# STM32_CAN-USB.net
KiCad netlist of a schematic drawn in EAGLE
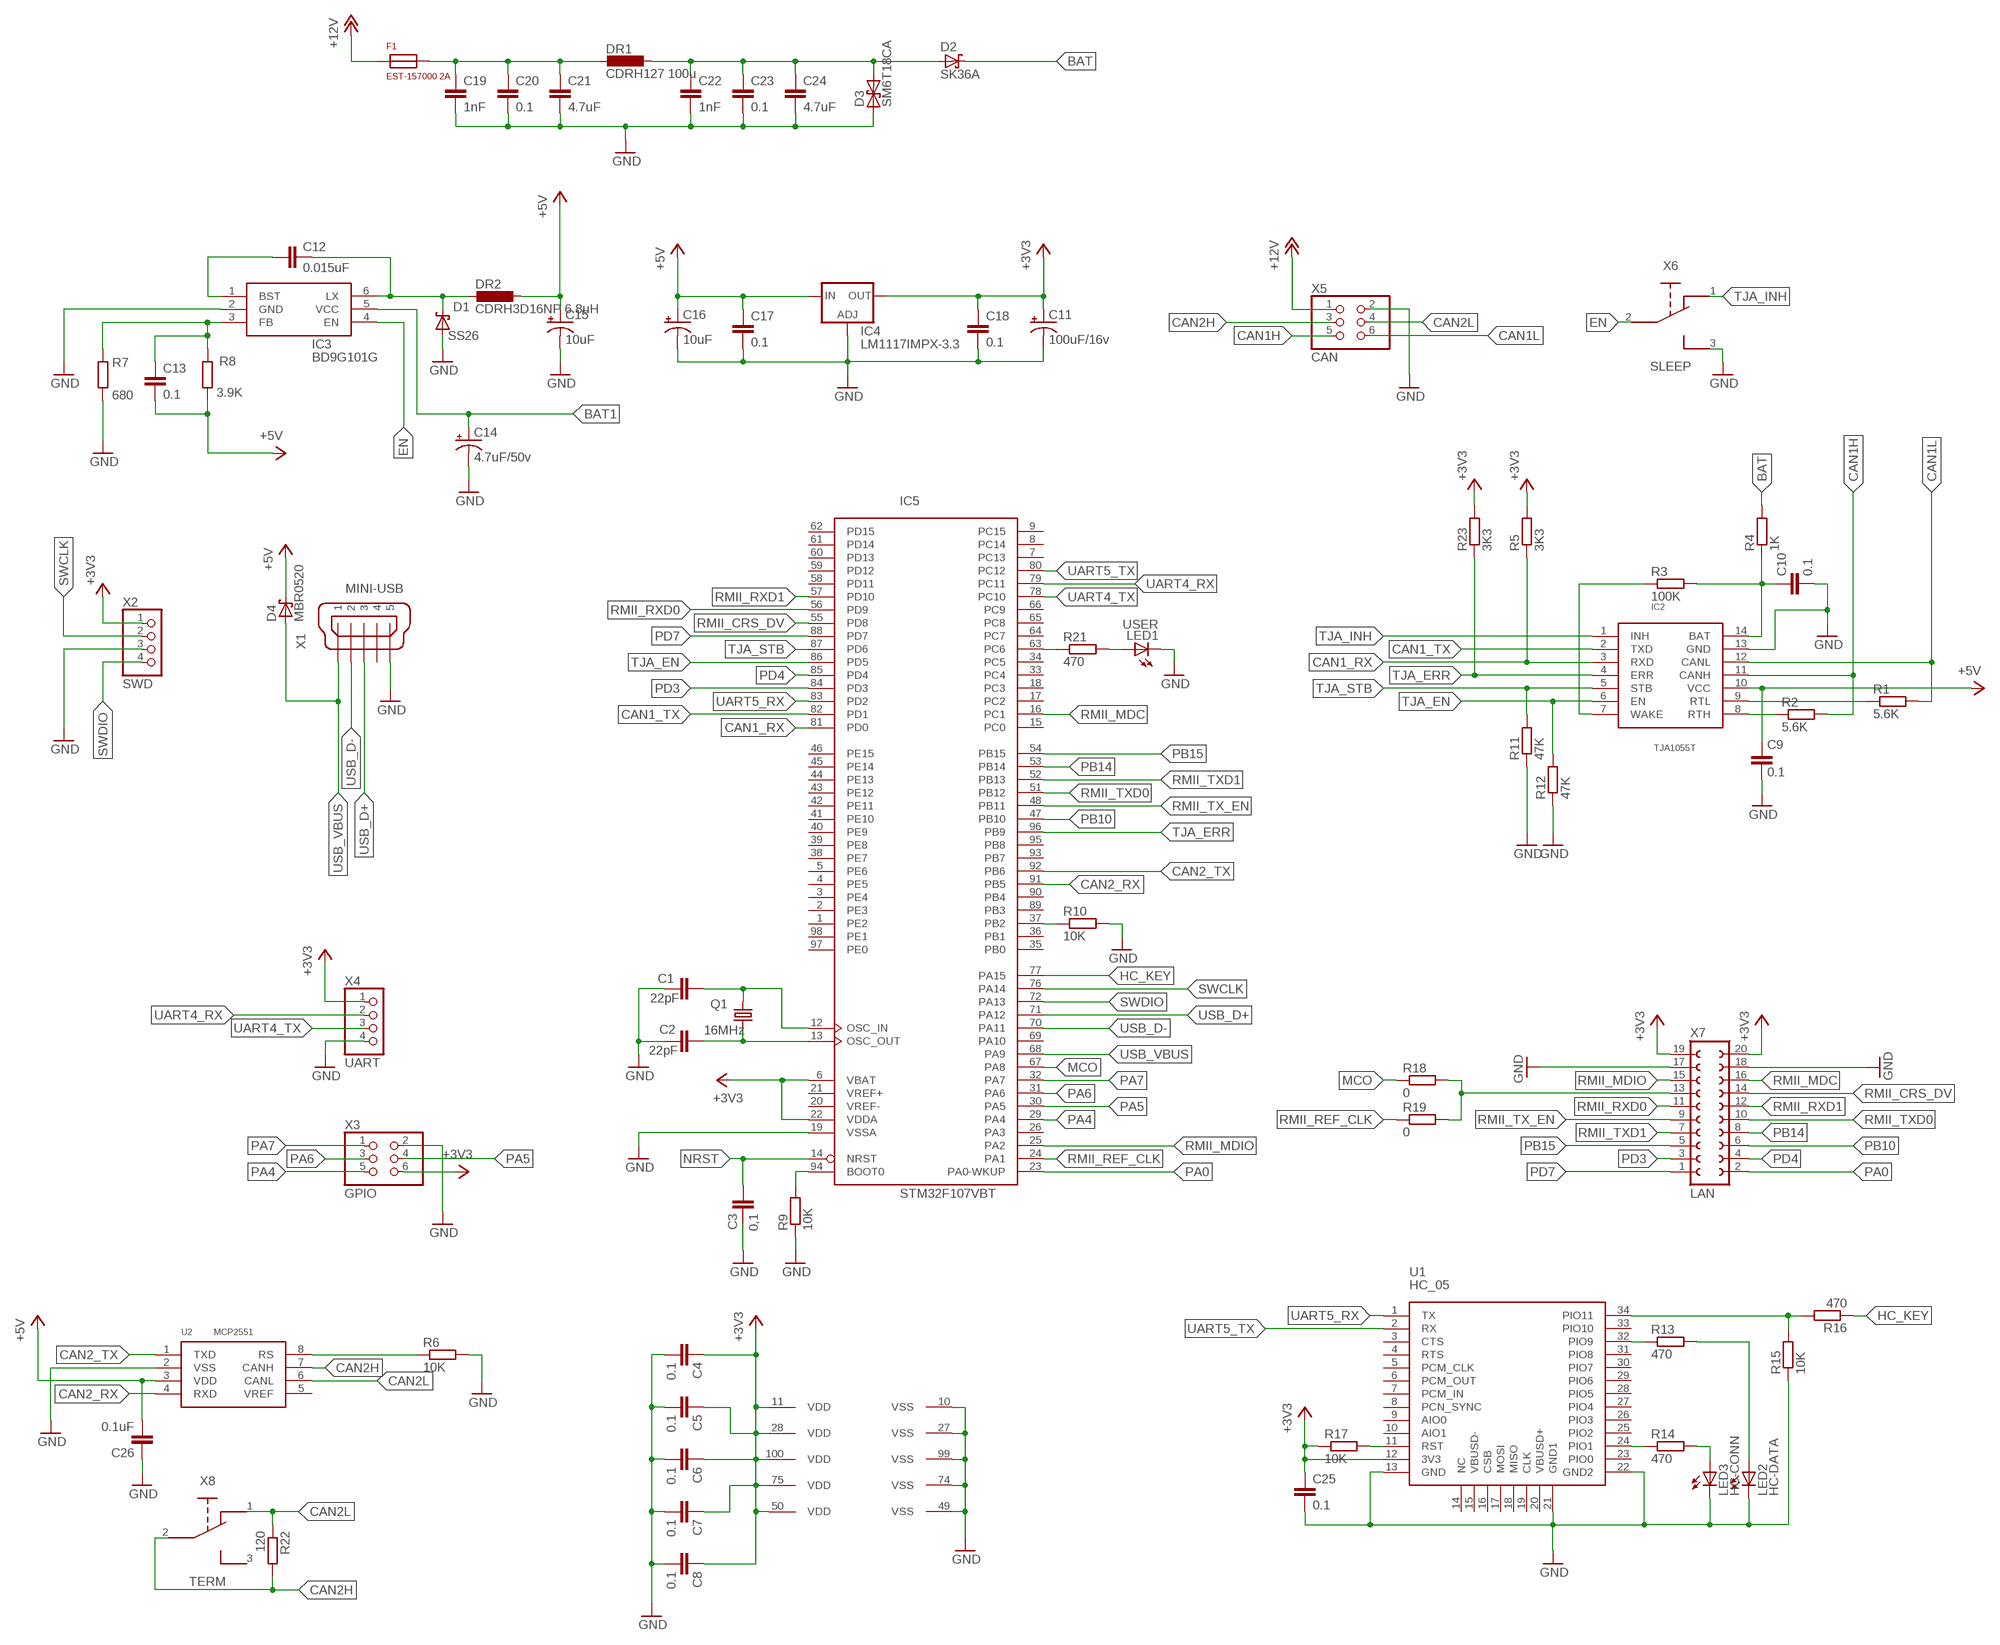
[diagram p0: schematic, sheet 1]

(export (version "E")
  (design (tool "Eeschema 10.0.6"))
  (components
    (comp (ref "C1")
      (value "22pF")
      (footprint "eagle-import:C0805")
      (libsource (lib "eagle-import") (part "C-EUC0805"))
    )
    (comp (ref "C2")
      (value "22pF")
      (footprint "eagle-import:C0805")
      (libsource (lib "eagle-import") (part "C-EUC0805"))
    )
    (comp (ref "C3")
      (value "0,1")
      (footprint "eagle-import:C0805")
      (libsource (lib "eagle-import") (part "C-EUC0805"))
    )
    (comp (ref "C4")
      (value "0.1")
      (footprint "eagle-import:C0805")
      (libsource (lib "eagle-import") (part "C-EUC0805"))
    )
    (comp (ref "C5")
      (value "0.1")
      (footprint "eagle-import:C0805")
      (libsource (lib "eagle-import") (part "C-EUC0805"))
    )
    (comp (ref "C6")
      (value "0.1")
      (footprint "eagle-import:C0805")
      (libsource (lib "eagle-import") (part "C-EUC0805"))
    )
    (comp (ref "C7")
      (value "0.1")
      (footprint "eagle-import:C0805")
      (libsource (lib "eagle-import") (part "C-EUC0805"))
    )
    (comp (ref "C8")
      (value "0.1")
      (footprint "eagle-import:C0805")
      (libsource (lib "eagle-import") (part "C-EUC0805"))
    )
    (comp (ref "C9")
      (value "0.1")
      (footprint "eagle-import:C0805")
      (libsource (lib "eagle-import") (part "C-EUC0805"))
    )
    (comp (ref "C10")
      (value "0.1")
      (footprint "eagle-import:C0805")
      (libsource (lib "eagle-import") (part "C-EUC0805"))
    )
    (comp (ref "C11")
      (value "100uF/16v")
      (footprint "eagle-import:153CLV-0605")
      (libsource (lib "eagle-import") (part "CPOL-US153CLV-0605"))
    )
    (comp (ref "C12")
      (value "0.015uF")
      (footprint "eagle-import:C0805")
      (libsource (lib "eagle-import") (part "C-EUC0805"))
    )
    (comp (ref "C13")
      (value "0.1")
      (footprint "eagle-import:C0805")
      (libsource (lib "eagle-import") (part "C-EUC0805"))
    )
    (comp (ref "C14")
      (value "4.7uF/50v")
      (footprint "eagle-import:153CLV-0605")
      (libsource (lib "eagle-import") (part "CPOL-US153CLV-0605"))
    )
    (comp (ref "C15")
      (value "10uF")
      (footprint "eagle-import:153CLV-0605")
      (libsource (lib "eagle-import") (part "CPOL-US153CLV-0605"))
    )
    (comp (ref "C16")
      (value "10uF")
      (footprint "eagle-import:153CLV-0605")
      (libsource (lib "eagle-import") (part "CPOL-US153CLV-0605"))
    )
    (comp (ref "C17")
      (value "0.1")
      (footprint "eagle-import:C0805")
      (libsource (lib "eagle-import") (part "C-EUC0805"))
    )
    (comp (ref "C18")
      (value "0.1")
      (footprint "eagle-import:C0805")
      (libsource (lib "eagle-import") (part "C-EUC0805"))
    )
    (comp (ref "C19")
      (value "1nF")
      (footprint "eagle-import:C0805")
      (libsource (lib "eagle-import") (part "C-EUC0805"))
    )
    (comp (ref "C20")
      (value "0.1")
      (footprint "eagle-import:C0805")
      (libsource (lib "eagle-import") (part "C-EUC0805"))
    )
    (comp (ref "C21")
      (value "4.7uF")
      (footprint "eagle-import:C0805")
      (libsource (lib "eagle-import") (part "C-EUC0805"))
    )
    (comp (ref "C22")
      (value "1nF")
      (footprint "eagle-import:C0805")
      (libsource (lib "eagle-import") (part "C-EUC0805"))
    )
    (comp (ref "C23")
      (value "0.1")
      (footprint "eagle-import:C0805")
      (libsource (lib "eagle-import") (part "C-EUC0805"))
    )
    (comp (ref "C24")
      (value "4.7uF")
      (footprint "eagle-import:C0805")
      (libsource (lib "eagle-import") (part "C-EUC0805"))
    )
    (comp (ref "C25")
      (value "0.1")
      (footprint "eagle-import:C0805")
      (libsource (lib "eagle-import") (part "C-EUC0805"))
    )
    (comp (ref "C26")
      (value "0.1uF")
      (footprint "eagle-import:C0805")
      (libsource (lib "eagle-import") (part "C-EUC0805"))
    )
    (comp (ref "D1")
      (value "SS26")
      (footprint "eagle-import:SMB")
      (libsource (lib "eagle-import") (part "SCHOTTKY-DIODESMD"))
    )
    (comp (ref "D2")
      (value "SK36A")
      (footprint "eagle-import:DO-214AC")
      (libsource (lib "eagle-import") (part "SK36A"))
    )
    (comp (ref "D3")
      (value "SM6T18CA")
      (footprint "eagle-import:DO214AA")
      (libsource (lib "eagle-import") (part "SM6T18CA"))
    )
    (comp (ref "D4")
      (value "MBR0520")
      (footprint "eagle-import:SOD123")
      (libsource (lib "eagle-import") (part "MBR0520"))
    )
    (comp (ref "DR1")
      (value "CDRH127 100u")
      (footprint "eagle-import:MS85")
      (libsource (lib "eagle-import") (part "CDRH127"))
    )
    (comp (ref "DR2")
      (value "CDRH3D16NP 6.8uH")
      (footprint "eagle-import:CDRH3D16NP")
      (libsource (lib "eagle-import") (part "CDRH3D16NP"))
    )
    (comp (ref "F1")
      (value "EST-157000 2A")
      (footprint "eagle-import:FUSE")
      (libsource (lib "eagle-import") (part "FUSE"))
    )
    (comp (ref "IC2")
      (value "TJA1055T")
      (footprint "eagle-import:SO-14W")
      (libsource (lib "eagle-import") (part "TJA1054T"))
    )
    (comp (ref "IC3")
      (value "BD9G101G")
      (footprint "eagle-import:SSOP6")
      (libsource (lib "eagle-import") (part "BD9G101G"))
    )
    (comp (ref "IC4")
      (value "LM1117IMPX-3.3")
      (footprint "eagle-import:SOT223")
      (libsource (lib "eagle-import") (part "LM1117IMPX-3.3"))
    )
    (comp (ref "IC5")
      (value "STM32F107VBT")
      (footprint "eagle-import:LQFP100")
      (libsource (lib "eagle-import") (part "STM32F107VTB"))
    )
    (comp (ref "LED1")
      (value "USER")
      (footprint "eagle-import:LED3MM")
      (libsource (lib "eagle-import") (part "LED3MM"))
    )
    (comp (ref "LED2")
      (value "HC-DATA")
      (footprint "eagle-import:LED3MM")
      (libsource (lib "eagle-import") (part "LED3MM"))
    )
    (comp (ref "LED3")
      (value "HC-CONN")
      (footprint "eagle-import:LED3MM")
      (libsource (lib "eagle-import") (part "LED3MM"))
    )
    (comp (ref "Q1")
      (value "16MHz")
      (footprint "eagle-import:HC49UP")
      (libsource (lib "eagle-import") (part "CRYSTALHC49UP"))
    )
    (comp (ref "R1")
      (value "5.6K")
      (footprint "eagle-import:R0805")
      (libsource (lib "eagle-import") (part "R-EU_R0805"))
    )
    (comp (ref "R2")
      (value "5.6K")
      (footprint "eagle-import:R0805")
      (libsource (lib "eagle-import") (part "R-EU_R0805"))
    )
    (comp (ref "R3")
      (value "100K")
      (footprint "eagle-import:R0805")
      (libsource (lib "eagle-import") (part "R-EU_R0805"))
    )
    (comp (ref "R4")
      (value "1K")
      (footprint "eagle-import:R0805")
      (libsource (lib "eagle-import") (part "R-EU_R0805"))
    )
    (comp (ref "R5")
      (value "3K3")
      (footprint "eagle-import:R0805")
      (libsource (lib "eagle-import") (part "R-EU_R0805"))
    )
    (comp (ref "R6")
      (value "10K")
      (footprint "eagle-import:R0805")
      (libsource (lib "eagle-import") (part "R-EU_R0805"))
    )
    (comp (ref "R7")
      (value "680")
      (footprint "eagle-import:R0805")
      (libsource (lib "eagle-import") (part "R-EU_R0805"))
    )
    (comp (ref "R8")
      (value "3.9K")
      (footprint "eagle-import:R0805")
      (libsource (lib "eagle-import") (part "R-EU_R0805"))
    )
    (comp (ref "R9")
      (value "10K")
      (footprint "eagle-import:R0805")
      (libsource (lib "eagle-import") (part "R-EU_R0805"))
    )
    (comp (ref "R10")
      (value "10K")
      (footprint "eagle-import:R0805")
      (libsource (lib "eagle-import") (part "R-EU_R0805"))
    )
    (comp (ref "R11")
      (value "47K")
      (footprint "eagle-import:R0805")
      (libsource (lib "eagle-import") (part "R-EU_R0805"))
    )
    (comp (ref "R12")
      (value "47K")
      (footprint "eagle-import:R0805")
      (libsource (lib "eagle-import") (part "R-EU_R0805"))
    )
    (comp (ref "R13")
      (value "470")
      (footprint "eagle-import:R0805")
      (libsource (lib "eagle-import") (part "R-EU_R0805"))
    )
    (comp (ref "R14")
      (value "470")
      (footprint "eagle-import:R0805")
      (libsource (lib "eagle-import") (part "R-EU_R0805"))
    )
    (comp (ref "R15")
      (value "10K")
      (footprint "eagle-import:R0805")
      (libsource (lib "eagle-import") (part "R-EU_R0805"))
    )
    (comp (ref "R16")
      (value "470")
      (footprint "eagle-import:R0805")
      (libsource (lib "eagle-import") (part "R-EU_R0805"))
    )
    (comp (ref "R17")
      (value "10K")
      (footprint "eagle-import:R0805")
      (libsource (lib "eagle-import") (part "R-EU_R0805"))
    )
    (comp (ref "R18")
      (value "0")
      (footprint "eagle-import:R0805")
      (libsource (lib "eagle-import") (part "R-EU_R0805"))
    )
    (comp (ref "R19")
      (value "0")
      (footprint "eagle-import:R0805")
      (libsource (lib "eagle-import") (part "R-EU_R0805"))
    )
    (comp (ref "R21")
      (value "470")
      (footprint "eagle-import:R0805")
      (libsource (lib "eagle-import") (part "R-EU_R0805"))
    )
    (comp (ref "R22")
      (value "120")
      (footprint "eagle-import:R0805")
      (libsource (lib "eagle-import") (part "R-EU_R0805"))
    )
    (comp (ref "R23")
      (value "3K3")
      (footprint "eagle-import:R0805")
      (libsource (lib "eagle-import") (part "R-EU_R0805"))
    )
    (comp (ref "U1")
      (value "HC_05")
      (footprint "eagle-import:BLUETOOTH_SMD")
      (libsource (lib "eagle-import") (part "HC_05"))
    )
    (comp (ref "U2")
      (value "MCP2551")
      (footprint "eagle-import:SO08")
      (fields (field (name "MPN") "MCP2551-I/SN"))
      (libsource (lib "eagle-import") (part "INTERFACE-MCP2551-I/SN(SOIC8)"))
    )
    (comp (ref "X1")
      (value "MINI-USB")
      (footprint "eagle-import:UX60-MB-5ST")
      (libsource (lib "eagle-import") (part "MINI-USB-UX60-MB-5ST"))
    )
    (comp (ref "X2")
      (value "SWD")
      (footprint "eagle-import:1X04")
      (libsource (lib "eagle-import") (part "PINHD-1X4"))
    )
    (comp (ref "X3")
      (value "GPIO")
      (footprint "eagle-import:2X03_90")
      (libsource (lib "eagle-import") (part "PINHD-2X3/90"))
    )
    (comp (ref "X4")
      (value "UART")
      (footprint "eagle-import:1X04_90")
      (libsource (lib "eagle-import") (part "PINHD-1X4/90"))
    )
    (comp (ref "X5")
      (value "CAN")
      (footprint "eagle-import:2X03_90")
      (libsource (lib "eagle-import") (part "PINHD-2X3/90"))
    )
    (comp (ref "X6")
      (value "SLEEP")
      (footprint "eagle-import:SS12F27")
      (libsource (lib "eagle-import") (part "SS12F27"))
    )
    (comp (ref "X7")
      (value "LAN")
      (footprint "eagle-import:FE10-2W")
      (libsource (lib "eagle-import") (part "FE10-2W"))
    )
    (comp (ref "X8")
      (value "TERM")
      (footprint "eagle-import:SS12F27")
      (libsource (lib "eagle-import") (part "SS12F27"))
    )
  )
  (nets
    (net (code "1") (name "+3V3") (class "Default")
      (node (ref "C11") (pin "+") (pinfunction "+_+") (pintype "passive"))
      (node (ref "C18") (pin "1") (pinfunction "1_1") (pintype "passive"))
      (node (ref "C25") (pin "1") (pinfunction "1_1") (pintype "passive"))
      (node (ref "C4") (pin "1") (pinfunction "1_1") (pintype "passive"))
      (node (ref "C5") (pin "1") (pinfunction "1_1") (pintype "passive"))
      (node (ref "C6") (pin "1") (pinfunction "1_1") (pintype "passive"))
      (node (ref "C7") (pin "1") (pinfunction "1_1") (pintype "passive"))
      (node (ref "C8") (pin "1") (pinfunction "1_1") (pintype "passive"))
      (node (ref "IC4") (pin "2") (pinfunction "OUT_2") (pintype "passive"))
      (node (ref "IC4") (pin "4") (pinfunction "OUT_4") (pintype "passive"))
      (node (ref "IC5") (pin "100") (pinfunction "VDD_100") (pintype "power_in"))
      (node (ref "IC5") (pin "11") (pinfunction "VDD_11") (pintype "power_in"))
      (node (ref "IC5") (pin "22") (pinfunction "VDDA_22") (pintype "power_in"))
      (node (ref "IC5") (pin "28") (pinfunction "VDD_28") (pintype "power_in"))
      (node (ref "IC5") (pin "50") (pinfunction "VDD_50") (pintype "power_in"))
      (node (ref "IC5") (pin "6") (pinfunction "VBAT_6") (pintype "power_in"))
      (node (ref "IC5") (pin "75") (pinfunction "VDD_75") (pintype "power_in"))
      (node (ref "R17") (pin "1") (pinfunction "1_1") (pintype "passive"))
      (node (ref "R23") (pin "2") (pinfunction "2_2") (pintype "passive"))
      (node (ref "R5") (pin "2") (pinfunction "2_2") (pintype "passive"))
      (node (ref "U1") (pin "12") (pinfunction "3V3_12") (pintype "bidirectional"))
      (node (ref "X2") (pin "1") (pinfunction "1_1") (pintype "passive"))
      (node (ref "X3") (pin "6") (pinfunction "6_6") (pintype "passive"))
      (node (ref "X4") (pin "1") (pinfunction "1_1") (pintype "passive"))
      (node (ref "X7") (pin "19") (pinfunction "19_19") (pintype "passive"))
      (node (ref "X7") (pin "20") (pinfunction "20_20") (pintype "passive"))
    )
    (net (code "2") (name "+5V") (class "Default")
      (node (ref "C13") (pin "2") (pinfunction "2_2") (pintype "passive"))
      (node (ref "C15") (pin "+") (pinfunction "+_+") (pintype "passive"))
      (node (ref "C16") (pin "+") (pinfunction "+_+") (pintype "passive"))
      (node (ref "C17") (pin "1") (pinfunction "1_1") (pintype "passive"))
      (node (ref "C26") (pin "2") (pinfunction "2_2") (pintype "passive"))
      (node (ref "C9") (pin "1") (pinfunction "1_1") (pintype "passive"))
      (node (ref "D4") (pin "C") (pinfunction "C_C") (pintype "passive"))
      (node (ref "DR2") (pin "P$2") (pinfunction "2_P$2") (pintype "passive"))
      (node (ref "IC2") (pin "10") (pinfunction "VCC_10") (pintype "power_in"))
      (node (ref "IC4") (pin "3") (pinfunction "IN_3") (pintype "input"))
      (node (ref "R8") (pin "1") (pinfunction "1_1") (pintype "passive"))
      (node (ref "U2") (pin "3") (pinfunction "VDD_3") (pintype "bidirectional"))
    )
    (net (code "3") (name "+12V") (class "Default")
      (node (ref "F1") (pin "P$1") (pinfunction "1_P$1") (pintype "power_in"))
      (node (ref "X5") (pin "1") (pinfunction "1_1") (pintype "passive"))
    )
    (net (code "4") (name "/VREF+") (class "Default")
      (node (ref "IC5") (pin "21") (pinfunction "VREF+_21") (pintype "power_in"))
    )
    (net (code "5") (name "/VREF-") (class "Default")
      (node (ref "IC5") (pin "20") (pinfunction "VREF-_20") (pintype "power_in"))
    )
    (net (code "6") (name "BAT") (class "Default")
      (node (ref "D2") (pin "C") (pinfunction "C_C") (pintype "passive"))
      (node (ref "R4") (pin "2") (pinfunction "2_2") (pintype "passive"))
    )
    (net (code "7") (name "BAT1") (class "Default")
      (node (ref "C14") (pin "+") (pinfunction "+_+") (pintype "passive"))
      (node (ref "C22") (pin "1") (pinfunction "1_1") (pintype "passive"))
      (node (ref "C23") (pin "1") (pinfunction "1_1") (pintype "passive"))
      (node (ref "C24") (pin "1") (pinfunction "1_1") (pintype "passive"))
      (node (ref "D2") (pin "A") (pinfunction "A_A") (pintype "passive"))
      (node (ref "D3") (pin "C") (pinfunction "2_C") (pintype "passive"))
      (node (ref "DR1") (pin "P$2") (pinfunction "2_P$2") (pintype "passive"))
      (node (ref "IC3") (pin "5") (pinfunction "VCC_5") (pintype "power_in"))
    )
    (net (code "8") (name "CAN1H") (class "Default")
      (node (ref "IC2") (pin "11") (pinfunction "CANH_11") (pintype "bidirectional"))
      (node (ref "R2") (pin "2") (pinfunction "2_2") (pintype "passive"))
      (node (ref "X5") (pin "5") (pinfunction "5_5") (pintype "passive"))
    )
    (net (code "9") (name "CAN1L") (class "Default")
      (node (ref "IC2") (pin "12") (pinfunction "CANL_12") (pintype "bidirectional"))
      (node (ref "R1") (pin "2") (pinfunction "2_2") (pintype "passive"))
      (node (ref "X5") (pin "6") (pinfunction "6_6") (pintype "passive"))
    )
    (net (code "10") (name "CAN1_RX") (class "Default")
      (node (ref "IC2") (pin "3") (pinfunction "RXD_3") (pintype "bidirectional"))
      (node (ref "IC5") (pin "81") (pinfunction "PD0_81") (pintype "bidirectional"))
      (node (ref "R5") (pin "1") (pinfunction "1_1") (pintype "passive"))
    )
    (net (code "11") (name "CAN1_TX") (class "Default")
      (node (ref "IC2") (pin "2") (pinfunction "TXD_2") (pintype "bidirectional"))
      (node (ref "IC5") (pin "82") (pinfunction "PD1_82") (pintype "bidirectional"))
    )
    (net (code "12") (name "CAN2H") (class "Default")
      (node (ref "R22") (pin "2") (pinfunction "2_2") (pintype "passive"))
      (node (ref "U2") (pin "7") (pinfunction "CANH_7") (pintype "bidirectional"))
      (node (ref "X5") (pin "3") (pinfunction "3_3") (pintype "passive"))
      (node (ref "X8") (pin "2") (pinfunction "2_2") (pintype "bidirectional"))
    )
    (net (code "13") (name "CAN2L") (class "Default")
      (node (ref "R22") (pin "1") (pinfunction "1_1") (pintype "passive"))
      (node (ref "U2") (pin "6") (pinfunction "CANL_6") (pintype "bidirectional"))
      (node (ref "X5") (pin "4") (pinfunction "4_4") (pintype "passive"))
      (node (ref "X8") (pin "1") (pinfunction "1_1") (pintype "bidirectional"))
    )
    (net (code "14") (name "CAN2_RX") (class "Default")
      (node (ref "IC5") (pin "91") (pinfunction "PB5_91") (pintype "bidirectional"))
      (node (ref "U2") (pin "4") (pinfunction "RXD_4") (pintype "bidirectional"))
    )
    (net (code "15") (name "CAN2_TX") (class "Default")
      (node (ref "IC5") (pin "92") (pinfunction "PB6_92") (pintype "bidirectional"))
      (node (ref "U2") (pin "1") (pinfunction "TXD_1") (pintype "bidirectional"))
    )
    (net (code "16") (name "EN") (class "Default")
      (node (ref "IC3") (pin "4") (pinfunction "EN_4") (pintype "input"))
      (node (ref "X6") (pin "2") (pinfunction "2_2") (pintype "bidirectional"))
    )
    (net (code "17") (name "GND") (class "Default")
      (node (ref "C1") (pin "2") (pinfunction "2_2") (pintype "passive"))
      (node (ref "C10") (pin "2") (pinfunction "2_2") (pintype "passive"))
      (node (ref "C11") (pin "-") (pinfunction "-_-") (pintype "passive"))
      (node (ref "C14") (pin "-") (pinfunction "-_-") (pintype "passive"))
      (node (ref "C15") (pin "-") (pinfunction "-_-") (pintype "passive"))
      (node (ref "C16") (pin "-") (pinfunction "-_-") (pintype "passive"))
      (node (ref "C17") (pin "2") (pinfunction "2_2") (pintype "passive"))
      (node (ref "C18") (pin "2") (pinfunction "2_2") (pintype "passive"))
      (node (ref "C19") (pin "2") (pinfunction "2_2") (pintype "passive"))
      (node (ref "C2") (pin "2") (pinfunction "2_2") (pintype "passive"))
      (node (ref "C20") (pin "2") (pinfunction "2_2") (pintype "passive"))
      (node (ref "C21") (pin "2") (pinfunction "2_2") (pintype "passive"))
      (node (ref "C22") (pin "2") (pinfunction "2_2") (pintype "passive"))
      (node (ref "C23") (pin "2") (pinfunction "2_2") (pintype "passive"))
      (node (ref "C24") (pin "2") (pinfunction "2_2") (pintype "passive"))
      (node (ref "C25") (pin "2") (pinfunction "2_2") (pintype "passive"))
      (node (ref "C26") (pin "1") (pinfunction "1_1") (pintype "passive"))
      (node (ref "C3") (pin "1") (pinfunction "1_1") (pintype "passive"))
      (node (ref "C4") (pin "2") (pinfunction "2_2") (pintype "passive"))
      (node (ref "C5") (pin "2") (pinfunction "2_2") (pintype "passive"))
      (node (ref "C6") (pin "2") (pinfunction "2_2") (pintype "passive"))
      (node (ref "C7") (pin "2") (pinfunction "2_2") (pintype "passive"))
      (node (ref "C8") (pin "2") (pinfunction "2_2") (pintype "passive"))
      (node (ref "C9") (pin "2") (pinfunction "2_2") (pintype "passive"))
      (node (ref "D1") (pin "A") (pinfunction "A_A") (pintype "passive"))
      (node (ref "D3") (pin "A") (pinfunction "1_A") (pintype "passive"))
      (node (ref "IC2") (pin "13") (pinfunction "GND_13") (pintype "power_in"))
      (node (ref "IC3") (pin "2") (pinfunction "GND_2") (pintype "power_in"))
      (node (ref "IC4") (pin "1") (pinfunction "ADJ_1") (pintype "input"))
      (node (ref "IC5") (pin "10") (pinfunction "VSS_10") (pintype "power_in"))
      (node (ref "IC5") (pin "19") (pinfunction "VSSA_19") (pintype "power_in"))
      (node (ref "IC5") (pin "27") (pinfunction "VSS_27") (pintype "power_in"))
      (node (ref "IC5") (pin "49") (pinfunction "VSS_49") (pintype "power_in"))
      (node (ref "IC5") (pin "74") (pinfunction "VSS_74") (pintype "power_in"))
      (node (ref "IC5") (pin "99") (pinfunction "VSS_99") (pintype "power_in"))
      (node (ref "LED1") (pin "K") (pinfunction "C_K") (pintype "passive"))
      (node (ref "LED2") (pin "K") (pinfunction "C_K") (pintype "passive"))
      (node (ref "LED3") (pin "K") (pinfunction "C_K") (pintype "passive"))
      (node (ref "R10") (pin "2") (pinfunction "2_2") (pintype "passive"))
      (node (ref "R11") (pin "1") (pinfunction "1_1") (pintype "passive"))
      (node (ref "R12") (pin "1") (pinfunction "1_1") (pintype "passive"))
      (node (ref "R15") (pin "1") (pinfunction "1_1") (pintype "passive"))
      (node (ref "R6") (pin "2") (pinfunction "2_2") (pintype "passive"))
      (node (ref "R7") (pin "1") (pinfunction "1_1") (pintype "passive"))
      (node (ref "R9") (pin "1") (pinfunction "1_1") (pintype "passive"))
      (node (ref "U1") (pin "13") (pinfunction "GND_13") (pintype "bidirectional"))
      (node (ref "U1") (pin "21") (pinfunction "GND1_21") (pintype "bidirectional"))
      (node (ref "U1") (pin "22") (pinfunction "GND2_22") (pintype "bidirectional"))
      (node (ref "U2") (pin "2") (pinfunction "VSS_2") (pintype "bidirectional"))
      (node (ref "X1") (pin "5") (pinfunction "5_5") (pintype "input"))
      (node (ref "X1") (pin "M1") (pinfunction "5_M1") (pintype "input"))
      (node (ref "X1") (pin "M2") (pinfunction "5_M2") (pintype "input"))
      (node (ref "X2") (pin "3") (pinfunction "3_3") (pintype "passive"))
      (node (ref "X3") (pin "2") (pinfunction "2_2") (pintype "passive"))
      (node (ref "X4") (pin "4") (pinfunction "4_4") (pintype "passive"))
      (node (ref "X5") (pin "2") (pinfunction "2_2") (pintype "passive"))
      (node (ref "X6") (pin "3") (pinfunction "3_3") (pintype "bidirectional"))
      (node (ref "X7") (pin "17") (pinfunction "17_17") (pintype "passive"))
      (node (ref "X7") (pin "18") (pinfunction "18_18") (pintype "passive"))
    )
    (net (code "18") (name "HC_KEY") (class "Default")
      (node (ref "IC5") (pin "77") (pinfunction "PA15_77") (pintype "bidirectional"))
      (node (ref "R16") (pin "1") (pinfunction "1_1") (pintype "passive"))
    )
    (net (code "19") (name "MCO") (class "Default")
      (node (ref "IC5") (pin "67") (pinfunction "PA8_67") (pintype "bidirectional"))
      (node (ref "R18") (pin "1") (pinfunction "1_1") (pintype "passive"))
    )
    (net (code "20") (name "NRST") (class "Default")
      (node (ref "C3") (pin "2") (pinfunction "2_2") (pintype "passive"))
      (node (ref "IC5") (pin "14") (pinfunction "NRST_14") (pintype "bidirectional"))
    )
    (net (code "21") (name "Net-(DR1-1)") (class "Default")
      (node (ref "C19") (pin "1") (pinfunction "1_1") (pintype "passive"))
      (node (ref "C20") (pin "1") (pinfunction "1_1") (pintype "passive"))
      (node (ref "C21") (pin "1") (pinfunction "1_1") (pintype "passive"))
      (node (ref "DR1") (pin "P$1") (pinfunction "1_P$1") (pintype "passive"))
      (node (ref "F1") (pin "P$2") (pinfunction "2_P$2") (pintype "passive"))
    )
    (net (code "22") (name "Net-(DR2-1)") (class "Default")
      (node (ref "C12") (pin "2") (pinfunction "2_2") (pintype "passive"))
      (node (ref "D1") (pin "C") (pinfunction "C_C") (pintype "passive"))
      (node (ref "DR2") (pin "P$1") (pinfunction "1_P$1") (pintype "passive"))
      (node (ref "IC3") (pin "6") (pinfunction "LX_6") (pintype "output"))
    )
    (net (code "23") (name "Net-(IC2-BAT)") (class "Default")
      (node (ref "C10") (pin "1") (pinfunction "1_1") (pintype "passive"))
      (node (ref "IC2") (pin "14") (pinfunction "BAT_14") (pintype "input"))
      (node (ref "R3") (pin "2") (pinfunction "2_2") (pintype "passive"))
      (node (ref "R4") (pin "1") (pinfunction "1_1") (pintype "passive"))
    )
    (net (code "24") (name "Net-(IC2-RTH)") (class "Default")
      (node (ref "IC2") (pin "8") (pinfunction "RTH_8") (pintype "bidirectional"))
      (node (ref "R2") (pin "1") (pinfunction "1_1") (pintype "passive"))
    )
    (net (code "25") (name "Net-(IC2-RTL)") (class "Default")
      (node (ref "IC2") (pin "9") (pinfunction "RTL_9") (pintype "bidirectional"))
      (node (ref "R1") (pin "1") (pinfunction "1_1") (pintype "passive"))
    )
    (net (code "26") (name "Net-(IC2-WAKE)") (class "Default")
      (node (ref "IC2") (pin "7") (pinfunction "WAKE_7") (pintype "input"))
      (node (ref "R3") (pin "1") (pinfunction "1_1") (pintype "passive"))
    )
    (net (code "27") (name "Net-(IC3-BST)") (class "Default")
      (node (ref "C12") (pin "1") (pinfunction "1_1") (pintype "passive"))
      (node (ref "IC3") (pin "1") (pinfunction "BST_1") (pintype "input"))
    )
    (net (code "28") (name "Net-(IC3-FB)") (class "Default")
      (node (ref "C13") (pin "1") (pinfunction "1_1") (pintype "passive"))
      (node (ref "IC3") (pin "3") (pinfunction "FB_3") (pintype "input"))
      (node (ref "R7") (pin "2") (pinfunction "2_2") (pintype "passive"))
      (node (ref "R8") (pin "2") (pinfunction "2_2") (pintype "passive"))
    )
    (net (code "29") (name "Net-(IC5A-BOOT0)") (class "Default")
      (node (ref "IC5") (pin "94") (pinfunction "BOOT0_94") (pintype "input"))
      (node (ref "R9") (pin "2") (pinfunction "2_2") (pintype "passive"))
    )
    (net (code "30") (name "Net-(IC5A-OSC_IN)") (class "Default")
      (node (ref "C1") (pin "1") (pinfunction "1_1") (pintype "passive"))
      (node (ref "IC5") (pin "12") (pinfunction "OSC_IN_12") (pintype "bidirectional"))
      (node (ref "Q1") (pin "2") (pinfunction "2_2") (pintype "passive"))
    )
    (net (code "31") (name "Net-(IC5A-OSC_OUT)") (class "Default")
      (node (ref "C2") (pin "1") (pinfunction "1_1") (pintype "passive"))
      (node (ref "IC5") (pin "13") (pinfunction "OSC_OUT_13") (pintype "bidirectional"))
      (node (ref "Q1") (pin "1") (pinfunction "1_1") (pintype "passive"))
    )
    (net (code "32") (name "Net-(IC5A-PB2)") (class "Default")
      (node (ref "IC5") (pin "37") (pinfunction "PB2_37") (pintype "bidirectional"))
      (node (ref "R10") (pin "1") (pinfunction "1_1") (pintype "passive"))
    )
    (net (code "33") (name "Net-(IC5A-PC6)") (class "Default")
      (node (ref "IC5") (pin "63") (pinfunction "PC6_63") (pintype "bidirectional"))
      (node (ref "R21") (pin "1") (pinfunction "1_1") (pintype "passive"))
    )
    (net (code "34") (name "Net-(LED1-PadA)") (class "Default")
      (node (ref "LED1") (pin "A") (pinfunction "A_A") (pintype "passive"))
      (node (ref "R21") (pin "2") (pinfunction "2_2") (pintype "passive"))
    )
    (net (code "35") (name "Net-(LED2-PadA)") (class "Default")
      (node (ref "LED2") (pin "A") (pinfunction "A_A") (pintype "passive"))
      (node (ref "R13") (pin "2") (pinfunction "2_2") (pintype "passive"))
    )
    (net (code "36") (name "Net-(LED3-PadA)") (class "Default")
      (node (ref "LED3") (pin "A") (pinfunction "A_A") (pintype "passive"))
      (node (ref "R14") (pin "2") (pinfunction "2_2") (pintype "passive"))
    )
    (net (code "37") (name "Net-(R18-Pad2)") (class "Default")
      (node (ref "R18") (pin "2") (pinfunction "2_2") (pintype "passive"))
      (node (ref "R19") (pin "2") (pinfunction "2_2") (pintype "passive"))
      (node (ref "X7") (pin "13") (pinfunction "13_13") (pintype "passive"))
    )
    (net (code "38") (name "Net-(U1-PIO1)") (class "Default")
      (node (ref "R14") (pin "1") (pinfunction "1_1") (pintype "passive"))
      (node (ref "U1") (pin "24") (pinfunction "PIO1_24") (pintype "bidirectional"))
    )
    (net (code "39") (name "Net-(U1-PIO9)") (class "Default")
      (node (ref "R13") (pin "1") (pinfunction "1_1") (pintype "passive"))
      (node (ref "U1") (pin "32") (pinfunction "PIO9_32") (pintype "bidirectional"))
    )
    (net (code "40") (name "Net-(U1-PIO11)") (class "Default")
      (node (ref "R15") (pin "2") (pinfunction "2_2") (pintype "passive"))
      (node (ref "R16") (pin "2") (pinfunction "2_2") (pintype "passive"))
      (node (ref "U1") (pin "34") (pinfunction "PIO11_34") (pintype "bidirectional"))
    )
    (net (code "41") (name "Net-(U1-RST)") (class "Default")
      (node (ref "R17") (pin "2") (pinfunction "2_2") (pintype "passive"))
      (node (ref "U1") (pin "11") (pinfunction "RST_11") (pintype "bidirectional"))
    )
    (net (code "42") (name "Net-(U2-RS)") (class "Default")
      (node (ref "R6") (pin "1") (pinfunction "1_1") (pintype "passive"))
      (node (ref "U2") (pin "8") (pinfunction "RS_8") (pintype "bidirectional"))
    )
    (net (code "43") (name "PA0") (class "Default")
      (node (ref "IC5") (pin "23") (pinfunction "PA0-WKUP_23") (pintype "bidirectional"))
      (node (ref "X7") (pin "2") (pinfunction "2_2") (pintype "passive"))
    )
    (net (code "44") (name "PA4") (class "Default")
      (node (ref "IC5") (pin "29") (pinfunction "PA4_29") (pintype "bidirectional"))
      (node (ref "X3") (pin "5") (pinfunction "5_5") (pintype "passive"))
    )
    (net (code "45") (name "PA5") (class "Default")
      (node (ref "IC5") (pin "30") (pinfunction "PA5_30") (pintype "bidirectional"))
      (node (ref "X3") (pin "4") (pinfunction "4_4") (pintype "passive"))
    )
    (net (code "46") (name "PA6") (class "Default")
      (node (ref "IC5") (pin "31") (pinfunction "PA6_31") (pintype "bidirectional"))
      (node (ref "X3") (pin "3") (pinfunction "3_3") (pintype "passive"))
    )
    (net (code "47") (name "PA7") (class "Default")
      (node (ref "IC5") (pin "32") (pinfunction "PA7_32") (pintype "bidirectional"))
      (node (ref "X3") (pin "1") (pinfunction "1_1") (pintype "passive"))
    )
    (net (code "48") (name "PB10") (class "Default")
      (node (ref "IC5") (pin "47") (pinfunction "PB10_47") (pintype "bidirectional"))
      (node (ref "X7") (pin "6") (pinfunction "6_6") (pintype "passive"))
    )
    (net (code "49") (name "PB14") (class "Default")
      (node (ref "IC5") (pin "53") (pinfunction "PB14_53") (pintype "bidirectional"))
      (node (ref "X7") (pin "8") (pinfunction "8_8") (pintype "passive"))
    )
    (net (code "50") (name "PB15") (class "Default")
      (node (ref "IC5") (pin "54") (pinfunction "PB15_54") (pintype "bidirectional"))
      (node (ref "X7") (pin "5") (pinfunction "5_5") (pintype "passive"))
    )
    (net (code "51") (name "PD3") (class "Default")
      (node (ref "IC5") (pin "84") (pinfunction "PD3_84") (pintype "bidirectional"))
      (node (ref "X7") (pin "3") (pinfunction "3_3") (pintype "passive"))
    )
    (net (code "52") (name "PD4") (class "Default")
      (node (ref "IC5") (pin "85") (pinfunction "PD4_85") (pintype "bidirectional"))
      (node (ref "X7") (pin "4") (pinfunction "4_4") (pintype "passive"))
    )
    (net (code "53") (name "PD7") (class "Default")
      (node (ref "IC5") (pin "88") (pinfunction "PD7_88") (pintype "bidirectional"))
      (node (ref "X7") (pin "1") (pinfunction "1_1") (pintype "passive"))
    )
    (net (code "54") (name "RMII_CRS_DV") (class "Default")
      (node (ref "IC5") (pin "55") (pinfunction "PD8_55") (pintype "bidirectional"))
      (node (ref "X7") (pin "14") (pinfunction "14_14") (pintype "passive"))
    )
    (net (code "55") (name "RMII_MDC") (class "Default")
      (node (ref "IC5") (pin "16") (pinfunction "PC1_16") (pintype "bidirectional"))
      (node (ref "X7") (pin "16") (pinfunction "16_16") (pintype "passive"))
    )
    (net (code "56") (name "RMII_MDIO") (class "Default")
      (node (ref "IC5") (pin "25") (pinfunction "PA2_25") (pintype "bidirectional"))
      (node (ref "X7") (pin "15") (pinfunction "15_15") (pintype "passive"))
    )
    (net (code "57") (name "RMII_REF_CLK") (class "Default")
      (node (ref "IC5") (pin "24") (pinfunction "PA1_24") (pintype "bidirectional"))
      (node (ref "R19") (pin "1") (pinfunction "1_1") (pintype "passive"))
    )
    (net (code "58") (name "RMII_RXD0") (class "Default")
      (node (ref "IC5") (pin "56") (pinfunction "PD9_56") (pintype "bidirectional"))
      (node (ref "X7") (pin "11") (pinfunction "11_11") (pintype "passive"))
    )
    (net (code "59") (name "RMII_RXD1") (class "Default")
      (node (ref "IC5") (pin "57") (pinfunction "PD10_57") (pintype "bidirectional"))
      (node (ref "X7") (pin "12") (pinfunction "12_12") (pintype "passive"))
    )
    (net (code "60") (name "RMII_TXD0") (class "Default")
      (node (ref "IC5") (pin "51") (pinfunction "PB12_51") (pintype "bidirectional"))
      (node (ref "X7") (pin "10") (pinfunction "10_10") (pintype "passive"))
    )
    (net (code "61") (name "RMII_TXD1") (class "Default")
      (node (ref "IC5") (pin "52") (pinfunction "PB13_52") (pintype "bidirectional"))
      (node (ref "X7") (pin "7") (pinfunction "7_7") (pintype "passive"))
    )
    (net (code "62") (name "RMII_TX_EN") (class "Default")
      (node (ref "IC5") (pin "48") (pinfunction "PB11_48") (pintype "bidirectional"))
      (node (ref "X7") (pin "9") (pinfunction "9_9") (pintype "passive"))
    )
    (net (code "63") (name "SWCLK") (class "Default")
      (node (ref "IC5") (pin "76") (pinfunction "PA14_76") (pintype "bidirectional"))
      (node (ref "X2") (pin "2") (pinfunction "2_2") (pintype "passive"))
    )
    (net (code "64") (name "SWDIO") (class "Default")
      (node (ref "IC5") (pin "72") (pinfunction "PA13_72") (pintype "bidirectional"))
      (node (ref "X2") (pin "4") (pinfunction "4_4") (pintype "passive"))
    )
    (net (code "65") (name "TJA_EN") (class "Default")
      (node (ref "IC2") (pin "6") (pinfunction "EN_6") (pintype "input"))
      (node (ref "IC5") (pin "86") (pinfunction "PD5_86") (pintype "bidirectional"))
      (node (ref "R12") (pin "2") (pinfunction "2_2") (pintype "passive"))
    )
    (net (code "66") (name "TJA_ERR") (class "Default")
      (node (ref "IC2") (pin "4") (pinfunction "ERR_4") (pintype "output"))
      (node (ref "IC5") (pin "96") (pinfunction "PB9_96") (pintype "bidirectional"))
      (node (ref "R23") (pin "1") (pinfunction "1_1") (pintype "passive"))
    )
    (net (code "67") (name "TJA_INH") (class "Default")
      (node (ref "IC2") (pin "1") (pinfunction "INH_1") (pintype "output"))
      (node (ref "X6") (pin "1") (pinfunction "1_1") (pintype "bidirectional"))
    )
    (net (code "68") (name "TJA_STB") (class "Default")
      (node (ref "IC2") (pin "5") (pinfunction "STB_5") (pintype "input"))
      (node (ref "IC5") (pin "87") (pinfunction "PD6_87") (pintype "bidirectional"))
      (node (ref "R11") (pin "2") (pinfunction "2_2") (pintype "passive"))
    )
    (net (code "69") (name "UART4_RX") (class "Default")
      (node (ref "IC5") (pin "79") (pinfunction "PC11_79") (pintype "bidirectional"))
      (node (ref "X4") (pin "2") (pinfunction "2_2") (pintype "passive"))
    )
    (net (code "70") (name "UART4_TX") (class "Default")
      (node (ref "IC5") (pin "78") (pinfunction "PC10_78") (pintype "bidirectional"))
      (node (ref "X4") (pin "3") (pinfunction "3_3") (pintype "passive"))
    )
    (net (code "71") (name "UART5_RX") (class "Default")
      (node (ref "IC5") (pin "83") (pinfunction "PD2_83") (pintype "bidirectional"))
      (node (ref "U1") (pin "1") (pinfunction "TX_1") (pintype "bidirectional"))
    )
    (net (code "72") (name "UART5_TX") (class "Default")
      (node (ref "IC5") (pin "80") (pinfunction "PC12_80") (pintype "bidirectional"))
      (node (ref "U1") (pin "2") (pinfunction "RX_2") (pintype "bidirectional"))
    )
    (net (code "73") (name "USB_D+") (class "Default")
      (node (ref "IC5") (pin "71") (pinfunction "PA12_71") (pintype "bidirectional"))
      (node (ref "X1") (pin "3") (pinfunction "3_3") (pintype "input"))
    )
    (net (code "74") (name "USB_D-") (class "Default")
      (node (ref "IC5") (pin "70") (pinfunction "PA11_70") (pintype "bidirectional"))
      (node (ref "X1") (pin "2") (pinfunction "2_2") (pintype "input"))
    )
    (net (code "75") (name "USB_VBUS") (class "Default")
      (node (ref "D4") (pin "A") (pinfunction "A_A") (pintype "passive"))
      (node (ref "IC5") (pin "68") (pinfunction "PA9_68") (pintype "bidirectional"))
      (node (ref "X1") (pin "1") (pinfunction "1_1") (pintype "input"))
    )
    (net (code "76") (name "unconnected-(IC5A-PA3-Pad26)") (class "Default")
      (node (ref "IC5") (pin "26") (pinfunction "PA3_26") (pintype "bidirectional"))
    )
    (net (code "77") (name "unconnected-(IC5A-PA10-Pad69)") (class "Default")
      (node (ref "IC5") (pin "69") (pinfunction "PA10_69") (pintype "bidirectional"))
    )
    (net (code "78") (name "unconnected-(IC5A-PB0-Pad35)") (class "Default")
      (node (ref "IC5") (pin "35") (pinfunction "PB0_35") (pintype "bidirectional"))
    )
    (net (code "79") (name "unconnected-(IC5A-PB1-Pad36)") (class "Default")
      (node (ref "IC5") (pin "36") (pinfunction "PB1_36") (pintype "bidirectional"))
    )
    (net (code "80") (name "unconnected-(IC5A-PB3-Pad89)") (class "Default")
      (node (ref "IC5") (pin "89") (pinfunction "PB3_89") (pintype "bidirectional"))
    )
    (net (code "81") (name "unconnected-(IC5A-PB4-Pad90)") (class "Default")
      (node (ref "IC5") (pin "90") (pinfunction "PB4_90") (pintype "bidirectional"))
    )
    (net (code "82") (name "unconnected-(IC5A-PB7-Pad93)") (class "Default")
      (node (ref "IC5") (pin "93") (pinfunction "PB7_93") (pintype "bidirectional"))
    )
    (net (code "83") (name "unconnected-(IC5A-PB8-Pad95)") (class "Default")
      (node (ref "IC5") (pin "95") (pinfunction "PB8_95") (pintype "bidirectional"))
    )
    (net (code "84") (name "unconnected-(IC5A-PC0-Pad15)") (class "Default")
      (node (ref "IC5") (pin "15") (pinfunction "PC0_15") (pintype "bidirectional"))
    )
    (net (code "85") (name "unconnected-(IC5A-PC2-Pad17)") (class "Default")
      (node (ref "IC5") (pin "17") (pinfunction "PC2_17") (pintype "bidirectional"))
    )
    (net (code "86") (name "unconnected-(IC5A-PC3-Pad18)") (class "Default")
      (node (ref "IC5") (pin "18") (pinfunction "PC3_18") (pintype "bidirectional"))
    )
    (net (code "87") (name "unconnected-(IC5A-PC4-Pad33)") (class "Default")
      (node (ref "IC5") (pin "33") (pinfunction "PC4_33") (pintype "bidirectional"))
    )
    (net (code "88") (name "unconnected-(IC5A-PC5-Pad34)") (class "Default")
      (node (ref "IC5") (pin "34") (pinfunction "PC5_34") (pintype "bidirectional"))
    )
    (net (code "89") (name "unconnected-(IC5A-PC7-Pad64)") (class "Default")
      (node (ref "IC5") (pin "64") (pinfunction "PC7_64") (pintype "bidirectional"))
    )
    (net (code "90") (name "unconnected-(IC5A-PC8-Pad65)") (class "Default")
      (node (ref "IC5") (pin "65") (pinfunction "PC8_65") (pintype "bidirectional"))
    )
    (net (code "91") (name "unconnected-(IC5A-PC9-Pad66)") (class "Default")
      (node (ref "IC5") (pin "66") (pinfunction "PC9_66") (pintype "bidirectional"))
    )
    (net (code "92") (name "unconnected-(IC5A-PC13-Pad7)") (class "Default")
      (node (ref "IC5") (pin "7") (pinfunction "PC13_7") (pintype "bidirectional"))
    )
    (net (code "93") (name "unconnected-(IC5A-PC14-Pad8)") (class "Default")
      (node (ref "IC5") (pin "8") (pinfunction "PC14_8") (pintype "bidirectional"))
    )
    (net (code "94") (name "unconnected-(IC5A-PC15-Pad9)") (class "Default")
      (node (ref "IC5") (pin "9") (pinfunction "PC15_9") (pintype "bidirectional"))
    )
    (net (code "95") (name "unconnected-(IC5A-PD11-Pad58)") (class "Default")
      (node (ref "IC5") (pin "58") (pinfunction "PD11_58") (pintype "bidirectional"))
    )
    (net (code "96") (name "unconnected-(IC5A-PD12-Pad59)") (class "Default")
      (node (ref "IC5") (pin "59") (pinfunction "PD12_59") (pintype "bidirectional"))
    )
    (net (code "97") (name "unconnected-(IC5A-PD13-Pad60)") (class "Default")
      (node (ref "IC5") (pin "60") (pinfunction "PD13_60") (pintype "bidirectional"))
    )
    (net (code "98") (name "unconnected-(IC5A-PD14-Pad61)") (class "Default")
      (node (ref "IC5") (pin "61") (pinfunction "PD14_61") (pintype "bidirectional"))
    )
    (net (code "99") (name "unconnected-(IC5A-PD15-Pad62)") (class "Default")
      (node (ref "IC5") (pin "62") (pinfunction "PD15_62") (pintype "bidirectional"))
    )
    (net (code "100") (name "unconnected-(IC5A-PE0-Pad97)") (class "Default")
      (node (ref "IC5") (pin "97") (pinfunction "PE0_97") (pintype "bidirectional"))
    )
    (net (code "101") (name "unconnected-(IC5A-PE1-Pad98)") (class "Default")
      (node (ref "IC5") (pin "98") (pinfunction "PE1_98") (pintype "bidirectional"))
    )
    (net (code "102") (name "unconnected-(IC5A-PE2-Pad1)") (class "Default")
      (node (ref "IC5") (pin "1") (pinfunction "PE2_1") (pintype "bidirectional"))
    )
    (net (code "103") (name "unconnected-(IC5A-PE3-Pad2)") (class "Default")
      (node (ref "IC5") (pin "2") (pinfunction "PE3_2") (pintype "bidirectional"))
    )
    (net (code "104") (name "unconnected-(IC5A-PE4-Pad3)") (class "Default")
      (node (ref "IC5") (pin "3") (pinfunction "PE4_3") (pintype "bidirectional"))
    )
    (net (code "105") (name "unconnected-(IC5A-PE5-Pad4)") (class "Default")
      (node (ref "IC5") (pin "4") (pinfunction "PE5_4") (pintype "bidirectional"))
    )
    (net (code "106") (name "unconnected-(IC5A-PE6-Pad5)") (class "Default")
      (node (ref "IC5") (pin "5") (pinfunction "PE6_5") (pintype "bidirectional"))
    )
    (net (code "107") (name "unconnected-(IC5A-PE7-Pad38)") (class "Default")
      (node (ref "IC5") (pin "38") (pinfunction "PE7_38") (pintype "bidirectional"))
    )
    (net (code "108") (name "unconnected-(IC5A-PE8-Pad39)") (class "Default")
      (node (ref "IC5") (pin "39") (pinfunction "PE8_39") (pintype "bidirectional"))
    )
    (net (code "109") (name "unconnected-(IC5A-PE9-Pad40)") (class "Default")
      (node (ref "IC5") (pin "40") (pinfunction "PE9_40") (pintype "bidirectional"))
    )
    (net (code "110") (name "unconnected-(IC5A-PE10-Pad41)") (class "Default")
      (node (ref "IC5") (pin "41") (pinfunction "PE10_41") (pintype "bidirectional"))
    )
    (net (code "111") (name "unconnected-(IC5A-PE11-Pad42)") (class "Default")
      (node (ref "IC5") (pin "42") (pinfunction "PE11_42") (pintype "bidirectional"))
    )
    (net (code "112") (name "unconnected-(IC5A-PE12-Pad43)") (class "Default")
      (node (ref "IC5") (pin "43") (pinfunction "PE12_43") (pintype "bidirectional"))
    )
    (net (code "113") (name "unconnected-(IC5A-PE13-Pad44)") (class "Default")
      (node (ref "IC5") (pin "44") (pinfunction "PE13_44") (pintype "bidirectional"))
    )
    (net (code "114") (name "unconnected-(IC5A-PE14-Pad45)") (class "Default")
      (node (ref "IC5") (pin "45") (pinfunction "PE14_45") (pintype "bidirectional"))
    )
    (net (code "115") (name "unconnected-(IC5A-PE15-Pad46)") (class "Default")
      (node (ref "IC5") (pin "46") (pinfunction "PE15_46") (pintype "bidirectional"))
    )
    (net (code "116") (name "unconnected-(U1-AIO0-Pad9)") (class "Default")
      (node (ref "U1") (pin "9") (pinfunction "AIO0_9") (pintype "bidirectional"))
    )
    (net (code "117") (name "unconnected-(U1-AIO1-Pad10)") (class "Default")
      (node (ref "U1") (pin "10") (pinfunction "AIO1_10") (pintype "bidirectional"))
    )
    (net (code "118") (name "unconnected-(U1-CLK-Pad19)") (class "Default")
      (node (ref "U1") (pin "19") (pinfunction "CLK_19") (pintype "bidirectional"))
    )
    (net (code "119") (name "unconnected-(U1-CSB-Pad16)") (class "Default")
      (node (ref "U1") (pin "16") (pinfunction "CSB_16") (pintype "bidirectional"))
    )
    (net (code "120") (name "unconnected-(U1-CTS-Pad3)") (class "Default")
      (node (ref "U1") (pin "3") (pinfunction "CTS_3") (pintype "bidirectional"))
    )
    (net (code "121") (name "unconnected-(U1-MISO-Pad18)") (class "Default")
      (node (ref "U1") (pin "18") (pinfunction "MISO_18") (pintype "bidirectional"))
    )
    (net (code "122") (name "unconnected-(U1-MOSI-Pad17)") (class "Default")
      (node (ref "U1") (pin "17") (pinfunction "MOSI_17") (pintype "bidirectional"))
    )
    (net (code "123") (name "unconnected-(U1-NC-Pad14)") (class "Default")
      (node (ref "U1") (pin "14") (pinfunction "NC_14") (pintype "bidirectional"))
    )
    (net (code "124") (name "unconnected-(U1-PCM_CLK-Pad5)") (class "Default")
      (node (ref "U1") (pin "5") (pinfunction "PCM_CLK_5") (pintype "bidirectional"))
    )
    (net (code "125") (name "unconnected-(U1-PCM_IN-Pad7)") (class "Default")
      (node (ref "U1") (pin "7") (pinfunction "PCM_IN_7") (pintype "bidirectional"))
    )
    (net (code "126") (name "unconnected-(U1-PCM_OUT-Pad6)") (class "Default")
      (node (ref "U1") (pin "6") (pinfunction "PCM_OUT_6") (pintype "bidirectional"))
    )
    (net (code "127") (name "unconnected-(U1-PCN_SYNC-Pad8)") (class "Default")
      (node (ref "U1") (pin "8") (pinfunction "PCN_SYNC_8") (pintype "bidirectional"))
    )
    (net (code "128") (name "unconnected-(U1-PIO0-Pad23)") (class "Default")
      (node (ref "U1") (pin "23") (pinfunction "PIO0_23") (pintype "bidirectional"))
    )
    (net (code "129") (name "unconnected-(U1-PIO2-Pad25)") (class "Default")
      (node (ref "U1") (pin "25") (pinfunction "PIO2_25") (pintype "bidirectional"))
    )
    (net (code "130") (name "unconnected-(U1-PIO3-Pad26)") (class "Default")
      (node (ref "U1") (pin "26") (pinfunction "PIO3_26") (pintype "bidirectional"))
    )
    (net (code "131") (name "unconnected-(U1-PIO4-Pad27)") (class "Default")
      (node (ref "U1") (pin "27") (pinfunction "PIO4_27") (pintype "bidirectional"))
    )
    (net (code "132") (name "unconnected-(U1-PIO5-Pad28)") (class "Default")
      (node (ref "U1") (pin "28") (pinfunction "PIO5_28") (pintype "bidirectional"))
    )
    (net (code "133") (name "unconnected-(U1-PIO6-Pad29)") (class "Default")
      (node (ref "U1") (pin "29") (pinfunction "PIO6_29") (pintype "bidirectional"))
    )
    (net (code "134") (name "unconnected-(U1-PIO7-Pad30)") (class "Default")
      (node (ref "U1") (pin "30") (pinfunction "PIO7_30") (pintype "bidirectional"))
    )
    (net (code "135") (name "unconnected-(U1-PIO8-Pad31)") (class "Default")
      (node (ref "U1") (pin "31") (pinfunction "PIO8_31") (pintype "bidirectional"))
    )
    (net (code "136") (name "unconnected-(U1-PIO10-Pad33)") (class "Default")
      (node (ref "U1") (pin "33") (pinfunction "PIO10_33") (pintype "bidirectional"))
    )
    (net (code "137") (name "unconnected-(U1-RTS-Pad4)") (class "Default")
      (node (ref "U1") (pin "4") (pinfunction "RTS_4") (pintype "bidirectional"))
    )
    (net (code "138") (name "unconnected-(U1-VBUSD+-Pad20)") (class "Default")
      (node (ref "U1") (pin "20") (pinfunction "VBUSD+_20") (pintype "bidirectional"))
    )
    (net (code "139") (name "unconnected-(U1-VBUSD--Pad15)") (class "Default")
      (node (ref "U1") (pin "15") (pinfunction "VBUSD-_15") (pintype "bidirectional"))
    )
    (net (code "140") (name "unconnected-(U2-VREF-Pad5)") (class "Default")
      (node (ref "U2") (pin "5") (pinfunction "VREF_5") (pintype "bidirectional"))
    )
    (net (code "141") (name "unconnected-(X1-Pad4)") (class "Default")
      (node (ref "X1") (pin "4") (pinfunction "4_4") (pintype "input"))
    )
    (net (code "142") (name "unconnected-(X8-Pad3)") (class "Default")
      (node (ref "X8") (pin "3") (pinfunction "3_3") (pintype "bidirectional"))
    )
  )
)
